# flexdrive_rev0.net
KiCad netlist of a schematic drawn in EAGLE
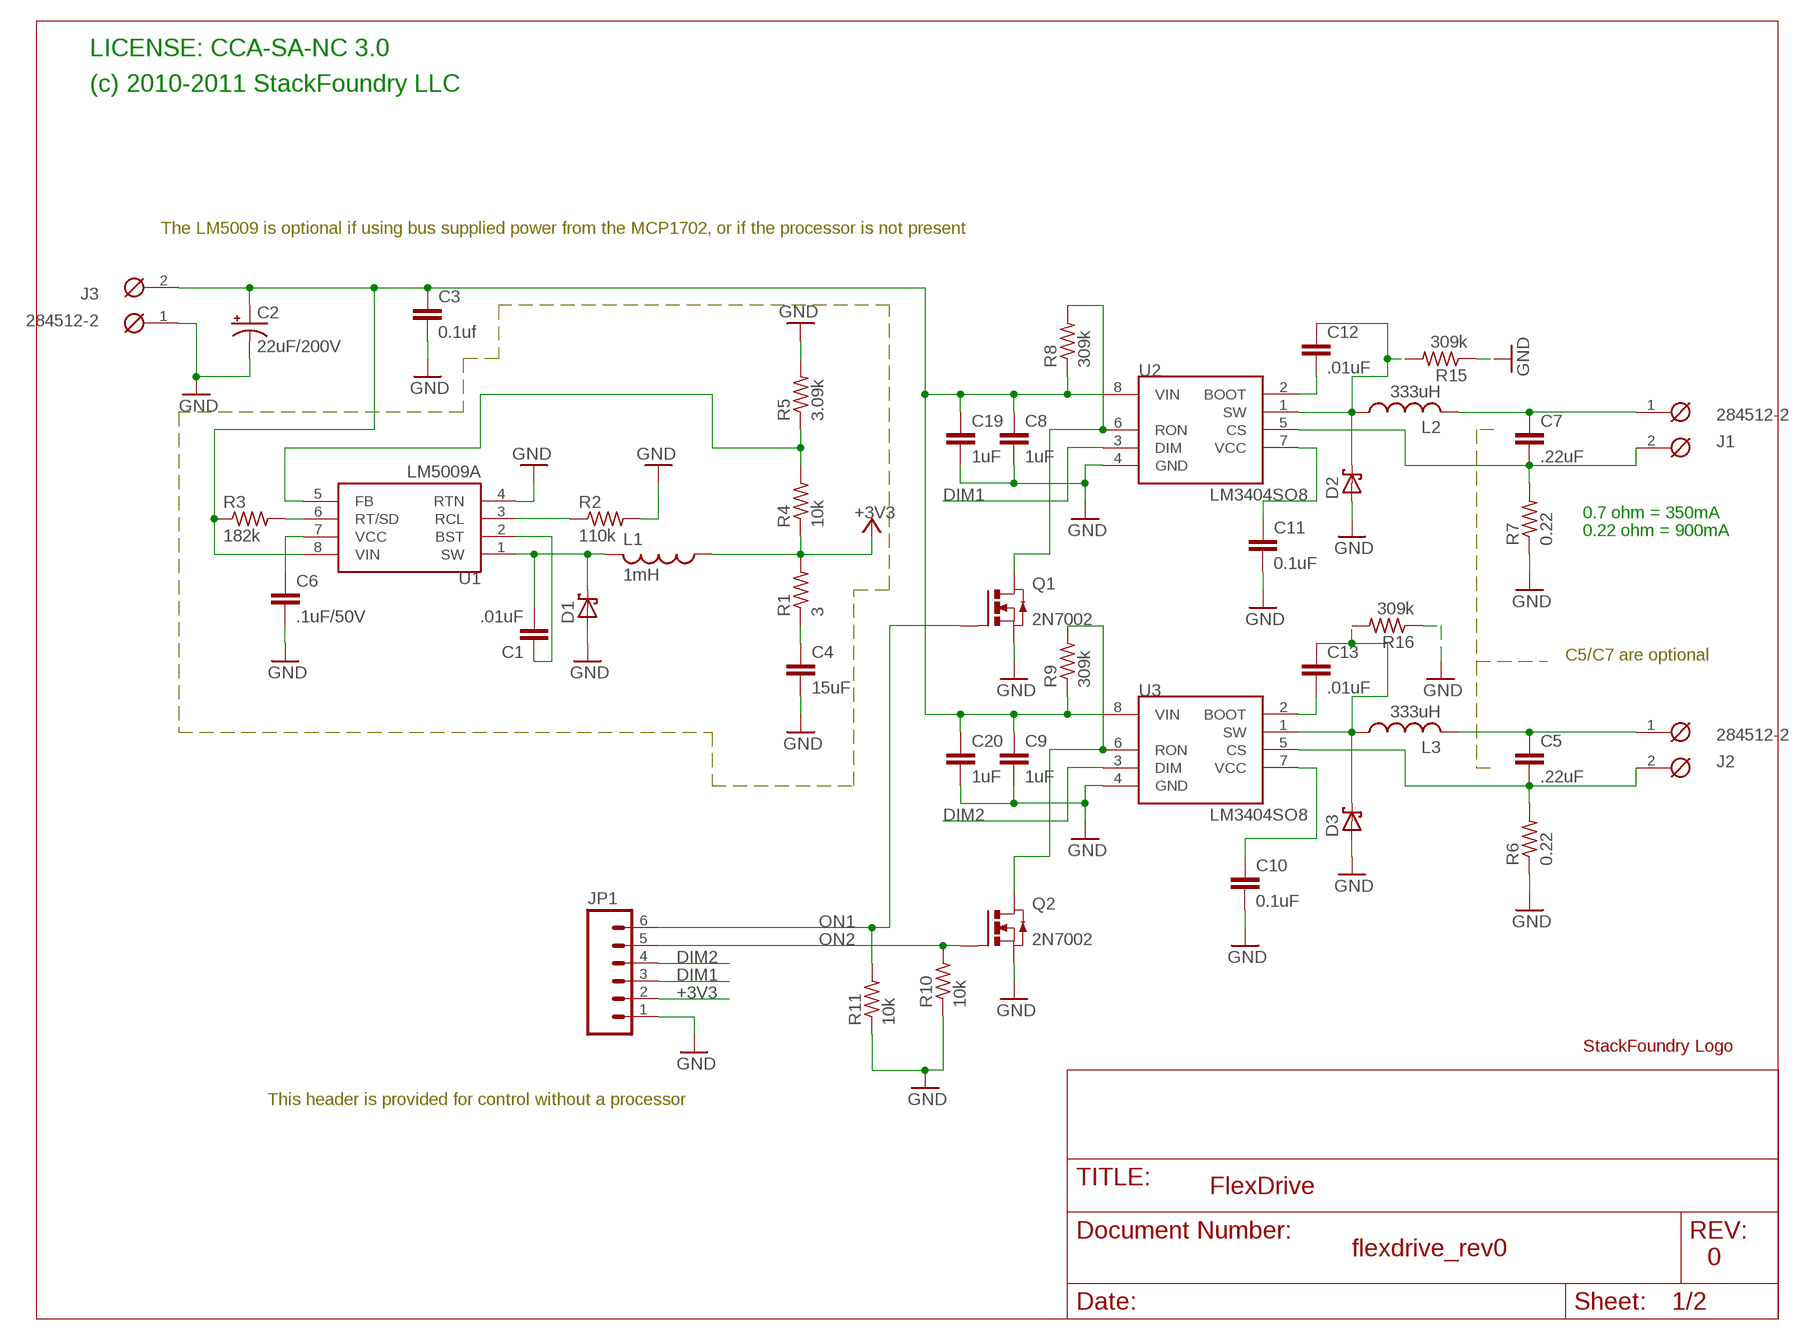
[diagram p0: schematic, sheet 1]
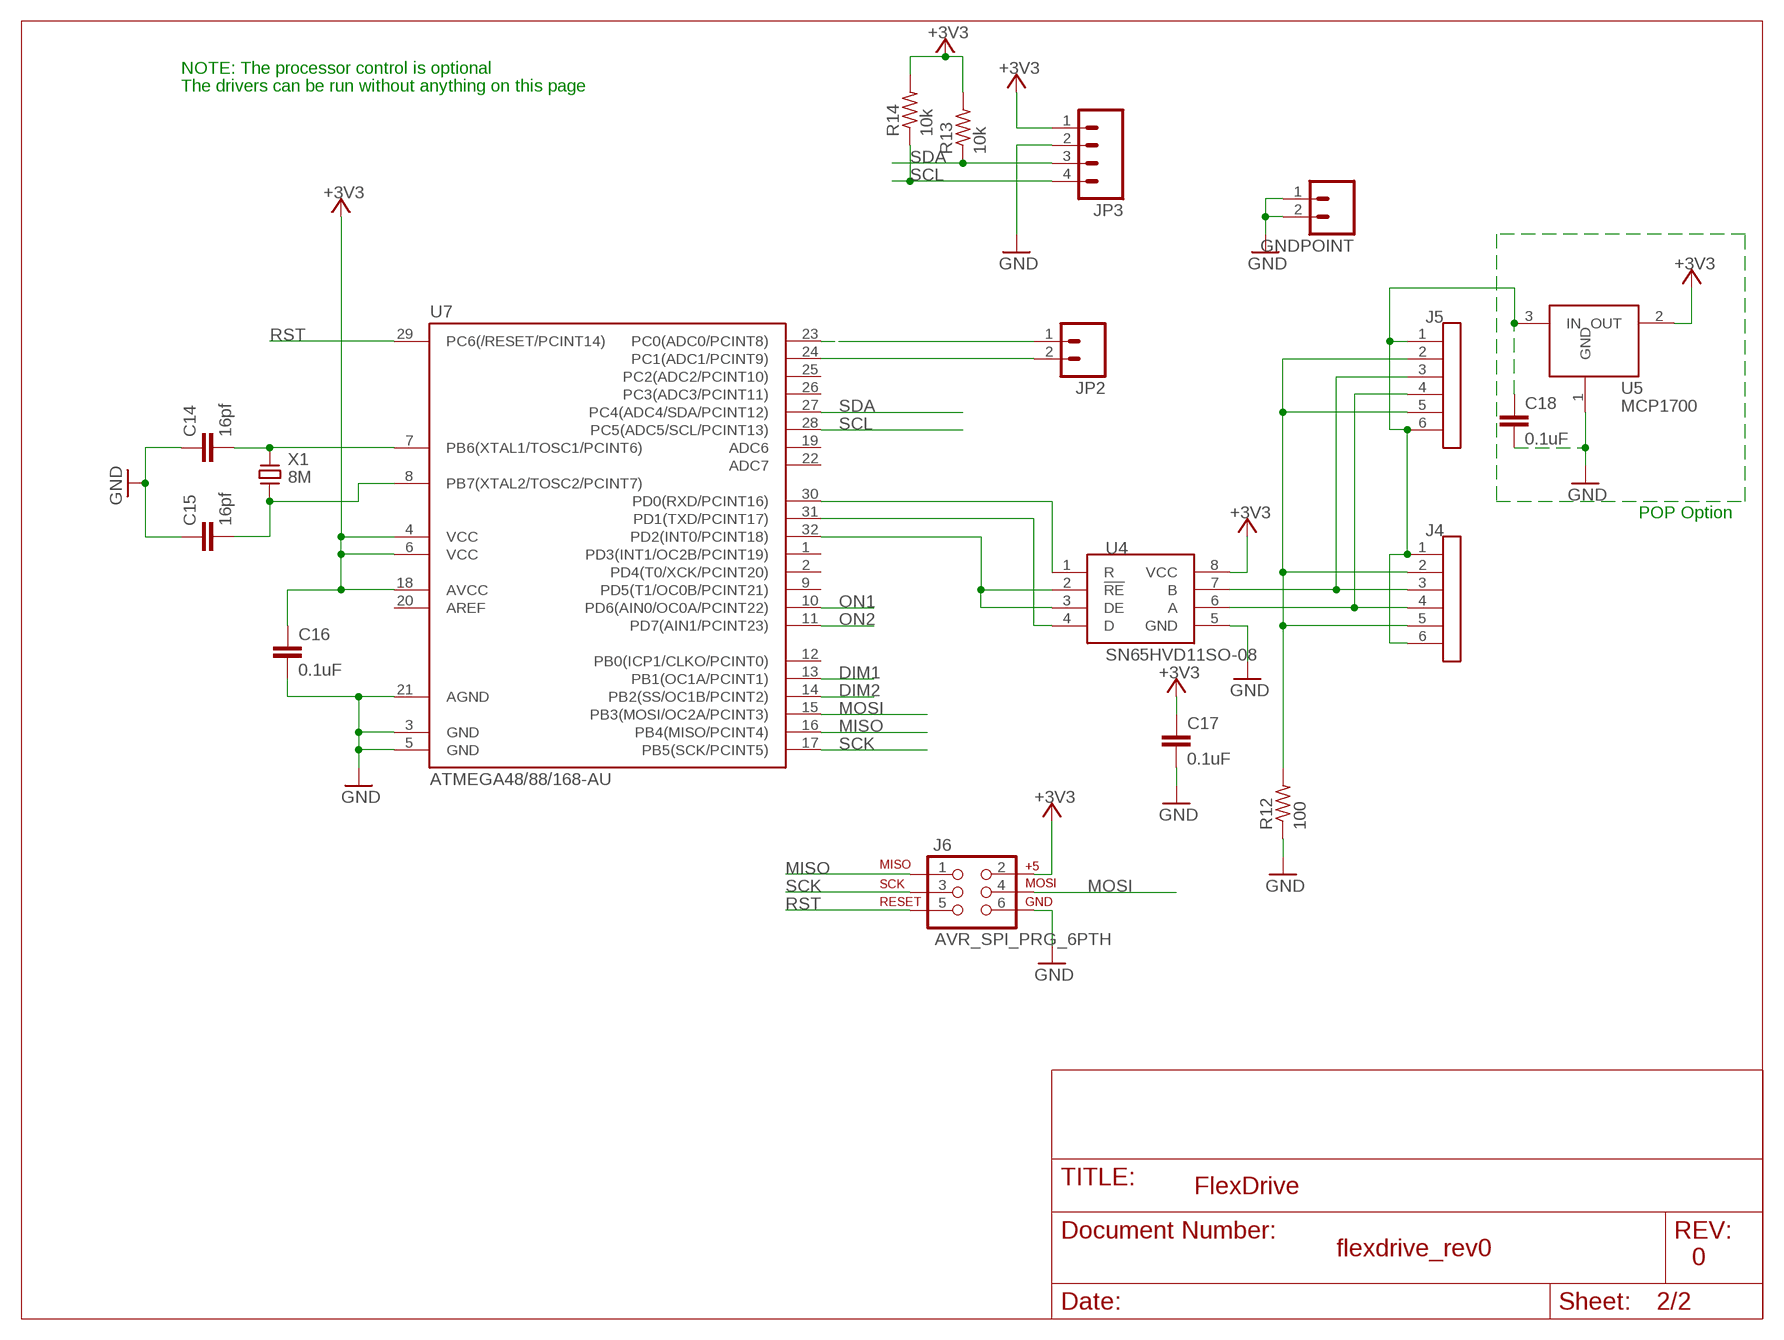
[diagram p1: schematic, sheet 2]

(export (version "E")
  (design (tool "Eeschema 10.0.6"))
  (components
    (comp (ref "C14")
      (value "16pf")
      (footprint "eagle-import:C0603")
      (libsource (lib "eagle-import") (part "C-EUC0603"))
    )
    (comp (ref "C15")
      (value "16pf")
      (footprint "eagle-import:C0603")
      (libsource (lib "eagle-import") (part "C-EUC0603"))
    )
    (comp (ref "C16")
      (value "0.1uF")
      (footprint "eagle-import:C0603")
      (libsource (lib "eagle-import") (part "C-EUC0603"))
    )
    (comp (ref "C17")
      (value "0.1uF")
      (footprint "eagle-import:C0603")
      (libsource (lib "eagle-import") (part "C-EUC0603"))
    )
    (comp (ref "C18")
      (value "0.1uF")
      (footprint "eagle-import:C0603")
      (libsource (lib "eagle-import") (part "C-EUC0603"))
    )
    (comp (ref "GNDPOINT")
      (value "M02PTH")
      (footprint "eagle-import:1X02")
      (libsource (lib "eagle-import") (part "M02PTH"))
    )
    (comp (ref "J4")
      (value "RJ12")
      (footprint "eagle-import:A-2004-RJ12")
      (libsource (lib "eagle-import") (part "RJ12"))
    )
    (comp (ref "J5")
      (value "RJ12")
      (footprint "eagle-import:A-2004-RJ12")
      (libsource (lib "eagle-import") (part "RJ12"))
    )
    (comp (ref "J6")
      (value "AVR_SPI_PRG_6PTH")
      (footprint "eagle-import:2X3")
      (libsource (lib "eagle-import") (part "AVR_SPI_PRG_6PTH"))
    )
    (comp (ref "JP2")
      (value "M02PTH")
      (footprint "eagle-import:1X02")
      (libsource (lib "eagle-import") (part "M02PTH"))
    )
    (comp (ref "JP3")
      (value "M04PTH")
      (footprint "eagle-import:1X04")
      (libsource (lib "eagle-import") (part "M04PTH"))
    )
    (comp (ref "R12")
      (value "100")
      (footprint "eagle-import:R0603")
      (libsource (lib "eagle-import") (part "R-US_R0603"))
    )
    (comp (ref "R13")
      (value "10k")
      (footprint "eagle-import:R0603")
      (libsource (lib "eagle-import") (part "R-US_R0603"))
    )
    (comp (ref "R14")
      (value "10k")
      (footprint "eagle-import:R0603")
      (libsource (lib "eagle-import") (part "R-US_R0603"))
    )
    (comp (ref "U4")
      (value "SN65HVD11SO-08")
      (footprint "eagle-import:SO-08")
      (libsource (lib "eagle-import") (part "SN65HVD11SO-08"))
    )
    (comp (ref "U5")
      (value "MCP1700")
      (footprint "eagle-import:SOT23")
      (libsource (lib "eagle-import") (part "MCP1700"))
    )
    (comp (ref "U7")
      (value "ATMEGA48/88/168-AU")
      (footprint "eagle-import:TQFP32-08")
      (libsource (lib "eagle-import") (part "ATMEGA48/88/168-AU"))
    )
    (comp (ref "X1")
      (value "8M")
      (footprint "eagle-import:HCM49")
      (libsource (lib "eagle-import") (part "HCM49_18.432M"))
    )
    (comp (ref "C1")
      (value ".01uF")
      (footprint "eagle-import:C0603")
      (libsource (lib "eagle-import") (part "C-EUC0603"))
    )
    (comp (ref "C2")
      (value "22uF/200V")
      (footprint "eagle-import:E5-10,5")
      (libsource (lib "eagle-import") (part "CPOL-USE5-10.5"))
    )
    (comp (ref "C3")
      (value "0.1uf")
      (footprint "eagle-import:C0805")
      (libsource (lib "eagle-import") (part "C-EUC0805"))
    )
    (comp (ref "C4")
      (value "15uF")
      (footprint "eagle-import:CT7343")
      (libsource (lib "eagle-import") (part "C-EUTANTD_R"))
    )
    (comp (ref "C5")
      (value ".22uF")
      (footprint "eagle-import:C1206")
      (libsource (lib "eagle-import") (part "C-EUC1206"))
    )
    (comp (ref "C6")
      (value ".1uF/50V")
      (footprint "eagle-import:C1206")
      (libsource (lib "eagle-import") (part "C-EUC1206"))
    )
    (comp (ref "C7")
      (value ".22uF")
      (footprint "eagle-import:C1206")
      (libsource (lib "eagle-import") (part "C-EUC1206"))
    )
    (comp (ref "C8")
      (value "1uF")
      (footprint "eagle-import:C1206")
      (libsource (lib "eagle-import") (part "C-EUC1206"))
    )
    (comp (ref "C9")
      (value "1uF")
      (footprint "eagle-import:C1206")
      (libsource (lib "eagle-import") (part "C-EUC1206"))
    )
    (comp (ref "C10")
      (value "0.1uF")
      (footprint "eagle-import:C1206")
      (libsource (lib "eagle-import") (part "C-EUC1206"))
    )
    (comp (ref "C11")
      (value "0.1uF")
      (footprint "eagle-import:C1206")
      (libsource (lib "eagle-import") (part "C-EUC1206"))
    )
    (comp (ref "C12")
      (value ".01uF")
      (footprint "eagle-import:C1206")
      (libsource (lib "eagle-import") (part "C-EUC1206"))
    )
    (comp (ref "C13")
      (value ".01uF")
      (footprint "eagle-import:C1206")
      (libsource (lib "eagle-import") (part "C-EUC1206"))
    )
    (comp (ref "C19")
      (value "1uF")
      (footprint "eagle-import:C1206")
      (libsource (lib "eagle-import") (part "C-EUC1206"))
    )
    (comp (ref "C20")
      (value "1uF")
      (footprint "eagle-import:C1206")
      (libsource (lib "eagle-import") (part "C-EUC1206"))
    )
    (comp (ref "D1")
      (value "SCHOTTKY-DIODESMA")
      (footprint "eagle-import:SMA")
      (libsource (lib "eagle-import") (part "SCHOTTKY-DIODESMA"))
    )
    (comp (ref "D2")
      (value "SCHOTTKY-DIODESMA")
      (footprint "eagle-import:SMA")
      (libsource (lib "eagle-import") (part "SCHOTTKY-DIODESMA"))
    )
    (comp (ref "D3")
      (value "SCHOTTKY-DIODESMA")
      (footprint "eagle-import:SMA")
      (libsource (lib "eagle-import") (part "SCHOTTKY-DIODESMA"))
    )
    (comp (ref "J1")
      (value "284512-2")
      (footprint "eagle-import:284512-2")
      (libsource (lib "eagle-import") (part "284512-2"))
    )
    (comp (ref "J2")
      (value "284512-2")
      (footprint "eagle-import:284512-2")
      (libsource (lib "eagle-import") (part "284512-2"))
    )
    (comp (ref "J3")
      (value "284512-2")
      (footprint "eagle-import:284512-2")
      (libsource (lib "eagle-import") (part "284512-2"))
    )
    (comp (ref "JP1")
      (value "M06SIP")
      (footprint "eagle-import:1X06")
      (libsource (lib "eagle-import") (part "M06SIP"))
    )
    (comp (ref "L1")
      (value "1mH")
      (footprint "eagle-import:MSS1246")
      (libsource (lib "eagle-import") (part "L-USMSS1246"))
    )
    (comp (ref "L2")
      (value "333uH")
      (footprint "eagle-import:DO5040H")
      (libsource (lib "eagle-import") (part "L-USDO5040H"))
    )
    (comp (ref "L3")
      (value "333uH")
      (footprint "eagle-import:DO5040H")
      (libsource (lib "eagle-import") (part "L-USDO5040H"))
    )
    (comp (ref "LOGO1")
      (value "SFLOGO")
      (footprint "eagle-import:SFLOGO")
      (libsource (lib "eagle-import") (part "SFLOGO"))
    )
    (comp (ref "Q1")
      (value "2N7002")
      (footprint "eagle-import:SOT23")
      (libsource (lib "eagle-import") (part "2N7002"))
    )
    (comp (ref "Q2")
      (value "2N7002")
      (footprint "eagle-import:SOT23")
      (libsource (lib "eagle-import") (part "2N7002"))
    )
    (comp (ref "R1")
      (value "3")
      (footprint "eagle-import:R0603")
      (libsource (lib "eagle-import") (part "R-US_R0603"))
    )
    (comp (ref "R2")
      (value "110k")
      (footprint "eagle-import:R0603")
      (libsource (lib "eagle-import") (part "R-US_R0603"))
    )
    (comp (ref "R3")
      (value "182k")
      (footprint "eagle-import:R0603")
      (libsource (lib "eagle-import") (part "R-US_R0603"))
    )
    (comp (ref "R4")
      (value "10k")
      (footprint "eagle-import:R0603")
      (libsource (lib "eagle-import") (part "R-US_R0603"))
    )
    (comp (ref "R5")
      (value "3.09k")
      (footprint "eagle-import:R0603")
      (libsource (lib "eagle-import") (part "R-US_R0603"))
    )
    (comp (ref "R6")
      (value "0.22")
      (footprint "eagle-import:R1206")
      (libsource (lib "eagle-import") (part "R-US_R1206"))
    )
    (comp (ref "R7")
      (value "0.22")
      (footprint "eagle-import:R1206")
      (libsource (lib "eagle-import") (part "R-US_R1206"))
    )
    (comp (ref "R8")
      (value "309k")
      (footprint "eagle-import:R0805")
      (libsource (lib "eagle-import") (part "R-US_R0805"))
    )
    (comp (ref "R9")
      (value "309k")
      (footprint "eagle-import:R0805")
      (libsource (lib "eagle-import") (part "R-US_R0805"))
    )
    (comp (ref "R10")
      (value "10k")
      (footprint "eagle-import:R0603")
      (libsource (lib "eagle-import") (part "R-US_R0603"))
    )
    (comp (ref "R11")
      (value "10k")
      (footprint "eagle-import:R0603")
      (libsource (lib "eagle-import") (part "R-US_R0603"))
    )
    (comp (ref "R15")
      (value "309k")
      (footprint "eagle-import:R0805")
      (libsource (lib "eagle-import") (part "R-US_R0805"))
    )
    (comp (ref "R16")
      (value "309k")
      (footprint "eagle-import:R0805")
      (libsource (lib "eagle-import") (part "R-US_R0805"))
    )
    (comp (ref "U1")
      (value "LM5009A")
      (footprint "eagle-import:MSOP-8")
      (libsource (lib "eagle-import") (part "LM5009A"))
    )
    (comp (ref "U2")
      (value "LM3404SO8")
      (footprint "eagle-import:SO08")
      (libsource (lib "eagle-import") (part "LM3404SO8"))
    )
    (comp (ref "U3")
      (value "LM3404SO8")
      (footprint "eagle-import:SO08")
      (libsource (lib "eagle-import") (part "LM3404SO8"))
    )
  )
  (nets
    (net (code "1") (name "+3V3") (class "Default")
      (node (ref "C16") (pin "1") (pinfunction "1_1") (pintype "passive"))
      (node (ref "C17") (pin "1") (pinfunction "1_1") (pintype "passive"))
      (node (ref "J6") (pin "2") (pinfunction "2_2") (pintype "passive"))
      (node (ref "JP1") (pin "2") (pinfunction "2_2") (pintype "passive"))
      (node (ref "JP3") (pin "1") (pinfunction "1_1") (pintype "passive"))
      (node (ref "L1") (pin "1") (pinfunction "1_1") (pintype "passive"))
      (node (ref "R1") (pin "2") (pinfunction "2_2") (pintype "passive"))
      (node (ref "R13") (pin "2") (pinfunction "2_2") (pintype "passive"))
      (node (ref "R14") (pin "2") (pinfunction "2_2") (pintype "passive"))
      (node (ref "R4") (pin "1") (pinfunction "1_1") (pintype "passive"))
      (node (ref "U4") (pin "8") (pinfunction "VCC_8") (pintype "bidirectional"))
      (node (ref "U5") (pin "2") (pinfunction "OUT_2") (pintype "bidirectional"))
      (node (ref "U7") (pin "18") (pinfunction "AVCC_18") (pintype "passive"))
      (node (ref "U7") (pin "4") (pinfunction "VCC_4") (pintype "power_in"))
      (node (ref "U7") (pin "6") (pinfunction "VCC_6") (pintype "power_in"))
    )
    (net (code "2") (name "DIM1") (class "Default")
      (node (ref "JP1") (pin "3") (pinfunction "3_3") (pintype "passive"))
      (node (ref "U2") (pin "3") (pinfunction "DIM_3") (pintype "bidirectional"))
      (node (ref "U7") (pin "13") (pinfunction "PB1(OC1A/PCINT1)_13") (pintype "bidirectional"))
    )
    (net (code "3") (name "DIM2") (class "Default")
      (node (ref "JP1") (pin "4") (pinfunction "4_4") (pintype "passive"))
      (node (ref "U3") (pin "3") (pinfunction "DIM_3") (pintype "bidirectional"))
      (node (ref "U7") (pin "14") (pinfunction "PB2(SS/OC1B/PCINT2)_14") (pintype "bidirectional"))
    )
    (net (code "4") (name "GND") (class "Default")
      (node (ref "C10") (pin "2") (pinfunction "2_2") (pintype "passive"))
      (node (ref "C11") (pin "2") (pinfunction "2_2") (pintype "passive"))
      (node (ref "C14") (pin "1") (pinfunction "1_1") (pintype "passive"))
      (node (ref "C15") (pin "1") (pinfunction "1_1") (pintype "passive"))
      (node (ref "C16") (pin "2") (pinfunction "2_2") (pintype "passive"))
      (node (ref "C17") (pin "2") (pinfunction "2_2") (pintype "passive"))
      (node (ref "C18") (pin "2") (pinfunction "2_2") (pintype "passive"))
      (node (ref "C19") (pin "2") (pinfunction "2_2") (pintype "passive"))
      (node (ref "C2") (pin "-") (pinfunction "-_-") (pintype "passive"))
      (node (ref "C20") (pin "2") (pinfunction "2_2") (pintype "passive"))
      (node (ref "C3") (pin "2") (pinfunction "2_2") (pintype "passive"))
      (node (ref "C4") (pin "-") (pinfunction "2_-") (pintype "passive"))
      (node (ref "C6") (pin "2") (pinfunction "2_2") (pintype "passive"))
      (node (ref "C8") (pin "2") (pinfunction "2_2") (pintype "passive"))
      (node (ref "C9") (pin "2") (pinfunction "2_2") (pintype "passive"))
      (node (ref "D1") (pin "A") (pinfunction "A_A") (pintype "passive"))
      (node (ref "D2") (pin "A") (pinfunction "A_A") (pintype "passive"))
      (node (ref "D3") (pin "A") (pinfunction "A_A") (pintype "passive"))
      (node (ref "GNDPOINT") (pin "1") (pinfunction "1_1") (pintype "passive"))
      (node (ref "GNDPOINT") (pin "2") (pinfunction "2_2") (pintype "passive"))
      (node (ref "J3") (pin "1") (pinfunction "P$1_1") (pintype "bidirectional"))
      (node (ref "J6") (pin "6") (pinfunction "6_6") (pintype "passive"))
      (node (ref "JP1") (pin "1") (pinfunction "1_1") (pintype "passive"))
      (node (ref "JP3") (pin "2") (pinfunction "2_2") (pintype "passive"))
      (node (ref "Q1") (pin "2") (pinfunction "S_2") (pintype "passive"))
      (node (ref "Q2") (pin "2") (pinfunction "S_2") (pintype "passive"))
      (node (ref "R10") (pin "1") (pinfunction "1_1") (pintype "passive"))
      (node (ref "R11") (pin "1") (pinfunction "1_1") (pintype "passive"))
      (node (ref "R12") (pin "1") (pinfunction "1_1") (pintype "passive"))
      (node (ref "R15") (pin "1") (pinfunction "1_1") (pintype "passive"))
      (node (ref "R16") (pin "1") (pinfunction "1_1") (pintype "passive"))
      (node (ref "R2") (pin "2") (pinfunction "2_2") (pintype "passive"))
      (node (ref "R5") (pin "2") (pinfunction "2_2") (pintype "passive"))
      (node (ref "R6") (pin "1") (pinfunction "1_1") (pintype "passive"))
      (node (ref "R7") (pin "1") (pinfunction "1_1") (pintype "passive"))
      (node (ref "U1") (pin "4") (pinfunction "RTN_4") (pintype "bidirectional"))
      (node (ref "U2") (pin "4") (pinfunction "GND_4") (pintype "bidirectional"))
      (node (ref "U3") (pin "4") (pinfunction "GND_4") (pintype "bidirectional"))
      (node (ref "U4") (pin "5") (pinfunction "GND_5") (pintype "bidirectional"))
      (node (ref "U5") (pin "1") (pinfunction "GND_1") (pintype "bidirectional"))
      (node (ref "U7") (pin "21") (pinfunction "AGND_21") (pintype "power_in"))
      (node (ref "U7") (pin "3") (pinfunction "GND_3") (pintype "power_in"))
      (node (ref "U7") (pin "5") (pinfunction "GND_5") (pintype "power_in"))
    )
    (net (code "5") (name "MISO") (class "Default")
      (node (ref "J6") (pin "1") (pinfunction "1_1") (pintype "passive"))
      (node (ref "U7") (pin "16") (pinfunction "PB4(MISO/PCINT4)_16") (pintype "bidirectional"))
    )
    (net (code "6") (name "MOSI") (class "Default")
      (node (ref "J6") (pin "4") (pinfunction "4_4") (pintype "passive"))
      (node (ref "U7") (pin "15") (pinfunction "PB3(MOSI/OC2A/PCINT3)_15") (pintype "bidirectional"))
    )
    (net (code "7") (name "Net-(C4-1)") (class "Default")
      (node (ref "C4") (pin "+") (pinfunction "1_+") (pintype "passive"))
      (node (ref "R1") (pin "1") (pinfunction "1_1") (pintype "passive"))
    )
    (net (code "8") (name "Net-(J1-P$1)") (class "Default")
      (node (ref "C7") (pin "1") (pinfunction "1_1") (pintype "passive"))
      (node (ref "J1") (pin "1") (pinfunction "P$1_1") (pintype "bidirectional"))
      (node (ref "L2") (pin "P$2") (pinfunction "2_P$2") (pintype "passive"))
    )
    (net (code "9") (name "Net-(J1-P$2)") (class "Default")
      (node (ref "C7") (pin "2") (pinfunction "2_2") (pintype "passive"))
      (node (ref "J1") (pin "2") (pinfunction "P$2_2") (pintype "bidirectional"))
      (node (ref "R7") (pin "2") (pinfunction "2_2") (pintype "passive"))
      (node (ref "U2") (pin "5") (pinfunction "CS_5") (pintype "bidirectional"))
    )
    (net (code "10") (name "Net-(J2-P$1)") (class "Default")
      (node (ref "C5") (pin "1") (pinfunction "1_1") (pintype "passive"))
      (node (ref "J2") (pin "1") (pinfunction "P$1_1") (pintype "bidirectional"))
      (node (ref "L3") (pin "P$2") (pinfunction "2_P$2") (pintype "passive"))
    )
    (net (code "11") (name "Net-(J2-P$2)") (class "Default")
      (node (ref "C5") (pin "2") (pinfunction "2_2") (pintype "passive"))
      (node (ref "J2") (pin "2") (pinfunction "P$2_2") (pintype "bidirectional"))
      (node (ref "R6") (pin "2") (pinfunction "2_2") (pintype "passive"))
      (node (ref "U3") (pin "5") (pinfunction "CS_5") (pintype "bidirectional"))
    )
    (net (code "12") (name "Net-(J3-P$2)") (class "Default")
      (node (ref "C19") (pin "1") (pinfunction "1_1") (pintype "passive"))
      (node (ref "C2") (pin "+") (pinfunction "+_+") (pintype "passive"))
      (node (ref "C20") (pin "1") (pinfunction "1_1") (pintype "passive"))
      (node (ref "C3") (pin "1") (pinfunction "1_1") (pintype "passive"))
      (node (ref "C8") (pin "1") (pinfunction "1_1") (pintype "passive"))
      (node (ref "C9") (pin "1") (pinfunction "1_1") (pintype "passive"))
      (node (ref "J3") (pin "2") (pinfunction "P$2_2") (pintype "bidirectional"))
      (node (ref "R3") (pin "1") (pinfunction "1_1") (pintype "passive"))
      (node (ref "R8") (pin "1") (pinfunction "1_1") (pintype "passive"))
      (node (ref "R9") (pin "1") (pinfunction "1_1") (pintype "passive"))
      (node (ref "U1") (pin "8") (pinfunction "VIN_8") (pintype "bidirectional"))
      (node (ref "U2") (pin "8") (pinfunction "VIN_8") (pintype "bidirectional"))
      (node (ref "U3") (pin "8") (pinfunction "VIN_8") (pintype "bidirectional"))
    )
    (net (code "13") (name "Net-(J4-P$1)") (class "Default")
      (node (ref "C18") (pin "1") (pinfunction "1_1") (pintype "passive"))
      (node (ref "J4") (pin "1") (pinfunction "P$1_1") (pintype "bidirectional"))
      (node (ref "J4") (pin "6") (pinfunction "P$6_6") (pintype "bidirectional"))
      (node (ref "J5") (pin "1") (pinfunction "P$1_1") (pintype "bidirectional"))
      (node (ref "J5") (pin "6") (pinfunction "P$6_6") (pintype "bidirectional"))
      (node (ref "U5") (pin "3") (pinfunction "IN_3") (pintype "bidirectional"))
    )
    (net (code "14") (name "Net-(J4-P$2)") (class "Default")
      (node (ref "J4") (pin "2") (pinfunction "P$2_2") (pintype "bidirectional"))
      (node (ref "J4") (pin "5") (pinfunction "P$5_5") (pintype "bidirectional"))
      (node (ref "J5") (pin "2") (pinfunction "P$2_2") (pintype "bidirectional"))
      (node (ref "J5") (pin "5") (pinfunction "P$5_5") (pintype "bidirectional"))
      (node (ref "R12") (pin "2") (pinfunction "2_2") (pintype "passive"))
    )
    (net (code "15") (name "Net-(J4-P$3)") (class "Default")
      (node (ref "J4") (pin "3") (pinfunction "P$3_3") (pintype "bidirectional"))
      (node (ref "J5") (pin "3") (pinfunction "P$3_3") (pintype "bidirectional"))
      (node (ref "U4") (pin "7") (pinfunction "B_7") (pintype "bidirectional"))
    )
    (net (code "16") (name "Net-(J4-P$4)") (class "Default")
      (node (ref "J4") (pin "4") (pinfunction "P$4_4") (pintype "bidirectional"))
      (node (ref "J5") (pin "4") (pinfunction "P$4_4") (pintype "bidirectional"))
      (node (ref "U4") (pin "6") (pinfunction "A_6") (pintype "bidirectional"))
    )
    (net (code "17") (name "Net-(L2-1)") (class "Default")
      (node (ref "C12") (pin "1") (pinfunction "1_1") (pintype "passive"))
      (node (ref "D2") (pin "C") (pinfunction "C_C") (pintype "passive"))
      (node (ref "L2") (pin "P$1") (pinfunction "1_P$1") (pintype "passive"))
      (node (ref "R15") (pin "2") (pinfunction "2_2") (pintype "passive"))
      (node (ref "U2") (pin "1") (pinfunction "SW_1") (pintype "bidirectional"))
    )
    (net (code "18") (name "Net-(L3-1)") (class "Default")
      (node (ref "C13") (pin "1") (pinfunction "1_1") (pintype "passive"))
      (node (ref "D3") (pin "C") (pinfunction "C_C") (pintype "passive"))
      (node (ref "L3") (pin "P$1") (pinfunction "1_P$1") (pintype "passive"))
      (node (ref "R16") (pin "2") (pinfunction "2_2") (pintype "passive"))
      (node (ref "U3") (pin "1") (pinfunction "SW_1") (pintype "bidirectional"))
    )
    (net (code "19") (name "Net-(Q1-D)") (class "Default")
      (node (ref "Q1") (pin "3") (pinfunction "D_3") (pintype "passive"))
      (node (ref "R8") (pin "2") (pinfunction "2_2") (pintype "passive"))
      (node (ref "U2") (pin "6") (pinfunction "RON_6") (pintype "bidirectional"))
    )
    (net (code "20") (name "Net-(Q2-D)") (class "Default")
      (node (ref "Q2") (pin "3") (pinfunction "D_3") (pintype "passive"))
      (node (ref "R9") (pin "2") (pinfunction "2_2") (pintype "passive"))
      (node (ref "U3") (pin "6") (pinfunction "RON_6") (pintype "bidirectional"))
    )
    (net (code "21") (name "Net-(U1-BST)") (class "Default")
      (node (ref "C1") (pin "1") (pinfunction "1_1") (pintype "passive"))
      (node (ref "U1") (pin "2") (pinfunction "BST_2") (pintype "bidirectional"))
    )
    (net (code "22") (name "Net-(U1-FB)") (class "Default")
      (node (ref "R4") (pin "2") (pinfunction "2_2") (pintype "passive"))
      (node (ref "R5") (pin "1") (pinfunction "1_1") (pintype "passive"))
      (node (ref "U1") (pin "5") (pinfunction "FB_5") (pintype "bidirectional"))
    )
    (net (code "23") (name "Net-(U1-RCL)") (class "Default")
      (node (ref "R2") (pin "1") (pinfunction "1_1") (pintype "passive"))
      (node (ref "U1") (pin "3") (pinfunction "RCL_3") (pintype "bidirectional"))
    )
    (net (code "24") (name "Net-(U1-RT{slash}SD)") (class "Default")
      (node (ref "R3") (pin "2") (pinfunction "2_2") (pintype "passive"))
      (node (ref "U1") (pin "6") (pinfunction "RT/SD_6") (pintype "bidirectional"))
    )
    (net (code "25") (name "Net-(U1-SW)") (class "Default")
      (node (ref "C1") (pin "2") (pinfunction "2_2") (pintype "passive"))
      (node (ref "D1") (pin "C") (pinfunction "C_C") (pintype "passive"))
      (node (ref "L1") (pin "2") (pinfunction "2_2") (pintype "passive"))
      (node (ref "U1") (pin "1") (pinfunction "SW_1") (pintype "bidirectional"))
    )
    (net (code "26") (name "Net-(U1-VCC)") (class "Default")
      (node (ref "C6") (pin "1") (pinfunction "1_1") (pintype "passive"))
      (node (ref "U1") (pin "7") (pinfunction "VCC_7") (pintype "bidirectional"))
    )
    (net (code "27") (name "Net-(U2-BOOT)") (class "Default")
      (node (ref "C12") (pin "2") (pinfunction "2_2") (pintype "passive"))
      (node (ref "U2") (pin "2") (pinfunction "BOOT_2") (pintype "bidirectional"))
    )
    (net (code "28") (name "Net-(U2-VCC)") (class "Default")
      (node (ref "C11") (pin "1") (pinfunction "1_1") (pintype "passive"))
      (node (ref "U2") (pin "7") (pinfunction "VCC_7") (pintype "bidirectional"))
    )
    (net (code "29") (name "Net-(U3-BOOT)") (class "Default")
      (node (ref "C13") (pin "2") (pinfunction "2_2") (pintype "passive"))
      (node (ref "U3") (pin "2") (pinfunction "BOOT_2") (pintype "bidirectional"))
    )
    (net (code "30") (name "Net-(U3-VCC)") (class "Default")
      (node (ref "C10") (pin "1") (pinfunction "1_1") (pintype "passive"))
      (node (ref "U3") (pin "7") (pinfunction "VCC_7") (pintype "bidirectional"))
    )
    (net (code "31") (name "Net-(U4-D)") (class "Default")
      (node (ref "U4") (pin "4") (pinfunction "D_4") (pintype "bidirectional"))
      (node (ref "U7") (pin "31") (pinfunction "PD1(TXD/PCINT17)_31") (pintype "bidirectional"))
    )
    (net (code "32") (name "Net-(U4-DE)") (class "Default")
      (node (ref "U4") (pin "2") (pinfunction "~{RE}_2") (pintype "bidirectional"))
      (node (ref "U4") (pin "3") (pinfunction "DE_3") (pintype "bidirectional"))
      (node (ref "U7") (pin "32") (pinfunction "PD2(INT0/PCINT18)_32") (pintype "bidirectional"))
    )
    (net (code "33") (name "Net-(U4-R)") (class "Default")
      (node (ref "U4") (pin "1") (pinfunction "R_1") (pintype "bidirectional"))
      (node (ref "U7") (pin "30") (pinfunction "PD0(RXD/PCINT16)_30") (pintype "bidirectional"))
    )
    (net (code "34") (name "Net-(U7-PB6(XTAL1{slash}TOSC1{slash}PCINT6))") (class "Default")
      (node (ref "C14") (pin "2") (pinfunction "2_2") (pintype "passive"))
      (node (ref "U7") (pin "7") (pinfunction "PB6(XTAL1/TOSC1/PCINT6)_7") (pintype "bidirectional"))
      (node (ref "X1") (pin "P$1") (pinfunction "P$1_P$1") (pintype "bidirectional"))
    )
    (net (code "35") (name "Net-(U7-PB7(XTAL2{slash}TOSC2{slash}PCINT7))") (class "Default")
      (node (ref "C15") (pin "2") (pinfunction "2_2") (pintype "passive"))
      (node (ref "U7") (pin "8") (pinfunction "PB7(XTAL2/TOSC2/PCINT7)_8") (pintype "bidirectional"))
      (node (ref "X1") (pin "P$2") (pinfunction "P$2_P$2") (pintype "bidirectional"))
    )
    (net (code "36") (name "Net-(U7-PC0(ADC0{slash}PCINT8))") (class "Default")
      (node (ref "JP2") (pin "1") (pinfunction "1_1") (pintype "passive"))
      (node (ref "U7") (pin "23") (pinfunction "PC0(ADC0/PCINT8)_23") (pintype "bidirectional"))
    )
    (net (code "37") (name "Net-(U7-PC1(ADC1{slash}PCINT9))") (class "Default")
      (node (ref "JP2") (pin "2") (pinfunction "2_2") (pintype "passive"))
      (node (ref "U7") (pin "24") (pinfunction "PC1(ADC1/PCINT9)_24") (pintype "bidirectional"))
    )
    (net (code "38") (name "ON1") (class "Default")
      (node (ref "JP1") (pin "6") (pinfunction "6_6") (pintype "passive"))
      (node (ref "Q1") (pin "1") (pinfunction "G_1") (pintype "passive"))
      (node (ref "R11") (pin "2") (pinfunction "2_2") (pintype "passive"))
      (node (ref "U7") (pin "10") (pinfunction "PD6(AIN0/OC0A/PCINT22)_10") (pintype "bidirectional"))
    )
    (net (code "39") (name "ON2") (class "Default")
      (node (ref "JP1") (pin "5") (pinfunction "5_5") (pintype "passive"))
      (node (ref "Q2") (pin "1") (pinfunction "G_1") (pintype "passive"))
      (node (ref "R10") (pin "2") (pinfunction "2_2") (pintype "passive"))
      (node (ref "U7") (pin "11") (pinfunction "PD7(AIN1/PCINT23)_11") (pintype "bidirectional"))
    )
    (net (code "40") (name "RST") (class "Default")
      (node (ref "J6") (pin "5") (pinfunction "5_5") (pintype "passive"))
      (node (ref "U7") (pin "29") (pinfunction "PC6(/RESET/PCINT14)_29") (pintype "bidirectional"))
    )
    (net (code "41") (name "SCK") (class "Default")
      (node (ref "J6") (pin "3") (pinfunction "3_3") (pintype "passive"))
      (node (ref "U7") (pin "17") (pinfunction "PB5(SCK/PCINT5)_17") (pintype "bidirectional"))
    )
    (net (code "42") (name "SCL") (class "Default")
      (node (ref "JP3") (pin "4") (pinfunction "4_4") (pintype "passive"))
      (node (ref "R14") (pin "1") (pinfunction "1_1") (pintype "passive"))
      (node (ref "U7") (pin "28") (pinfunction "PC5(ADC5/SCL/PCINT13)_28") (pintype "bidirectional"))
    )
    (net (code "43") (name "SDA") (class "Default")
      (node (ref "JP3") (pin "3") (pinfunction "3_3") (pintype "passive"))
      (node (ref "R13") (pin "1") (pinfunction "1_1") (pintype "passive"))
      (node (ref "U7") (pin "27") (pinfunction "PC4(ADC4/SDA/PCINT12)_27") (pintype "bidirectional"))
    )
    (net (code "44") (name "unconnected-(U7-ADC6-Pad19)") (class "Default")
      (node (ref "U7") (pin "19") (pinfunction "ADC6_19") (pintype "passive"))
    )
    (net (code "45") (name "unconnected-(U7-ADC7-Pad22)") (class "Default")
      (node (ref "U7") (pin "22") (pinfunction "ADC7_22") (pintype "passive"))
    )
    (net (code "46") (name "unconnected-(U7-AREF-Pad20)") (class "Default")
      (node (ref "U7") (pin "20") (pinfunction "AREF_20") (pintype "passive"))
    )
    (net (code "47") (name "unconnected-(U7-PB0(ICP1{slash}CLKO{slash}PCINT0)-Pad12)") (class "Default")
      (node (ref "U7") (pin "12") (pinfunction "PB0(ICP1/CLKO/PCINT0)_12") (pintype "bidirectional"))
    )
    (net (code "48") (name "unconnected-(U7-PC2(ADC2{slash}PCINT10)-Pad25)") (class "Default")
      (node (ref "U7") (pin "25") (pinfunction "PC2(ADC2/PCINT10)_25") (pintype "bidirectional"))
    )
    (net (code "49") (name "unconnected-(U7-PC3(ADC3{slash}PCINT11)-Pad26)") (class "Default")
      (node (ref "U7") (pin "26") (pinfunction "PC3(ADC3/PCINT11)_26") (pintype "bidirectional"))
    )
    (net (code "50") (name "unconnected-(U7-PD3(INT1{slash}OC2B{slash}PCINT19)-Pad1)") (class "Default")
      (node (ref "U7") (pin "1") (pinfunction "PD3(INT1/OC2B/PCINT19)_1") (pintype "bidirectional"))
    )
    (net (code "51") (name "unconnected-(U7-PD4(T0{slash}XCK{slash}PCINT20)-Pad2)") (class "Default")
      (node (ref "U7") (pin "2") (pinfunction "PD4(T0/XCK/PCINT20)_2") (pintype "bidirectional"))
    )
    (net (code "52") (name "unconnected-(U7-PD5(T1{slash}OC0B{slash}PCINT21)-Pad9)") (class "Default")
      (node (ref "U7") (pin "9") (pinfunction "PD5(T1/OC0B/PCINT21)_9") (pintype "bidirectional"))
    )
  )
)
